# RF_LoRa___GPS.net
KiCad netlist of a schematic drawn in Altium Designer
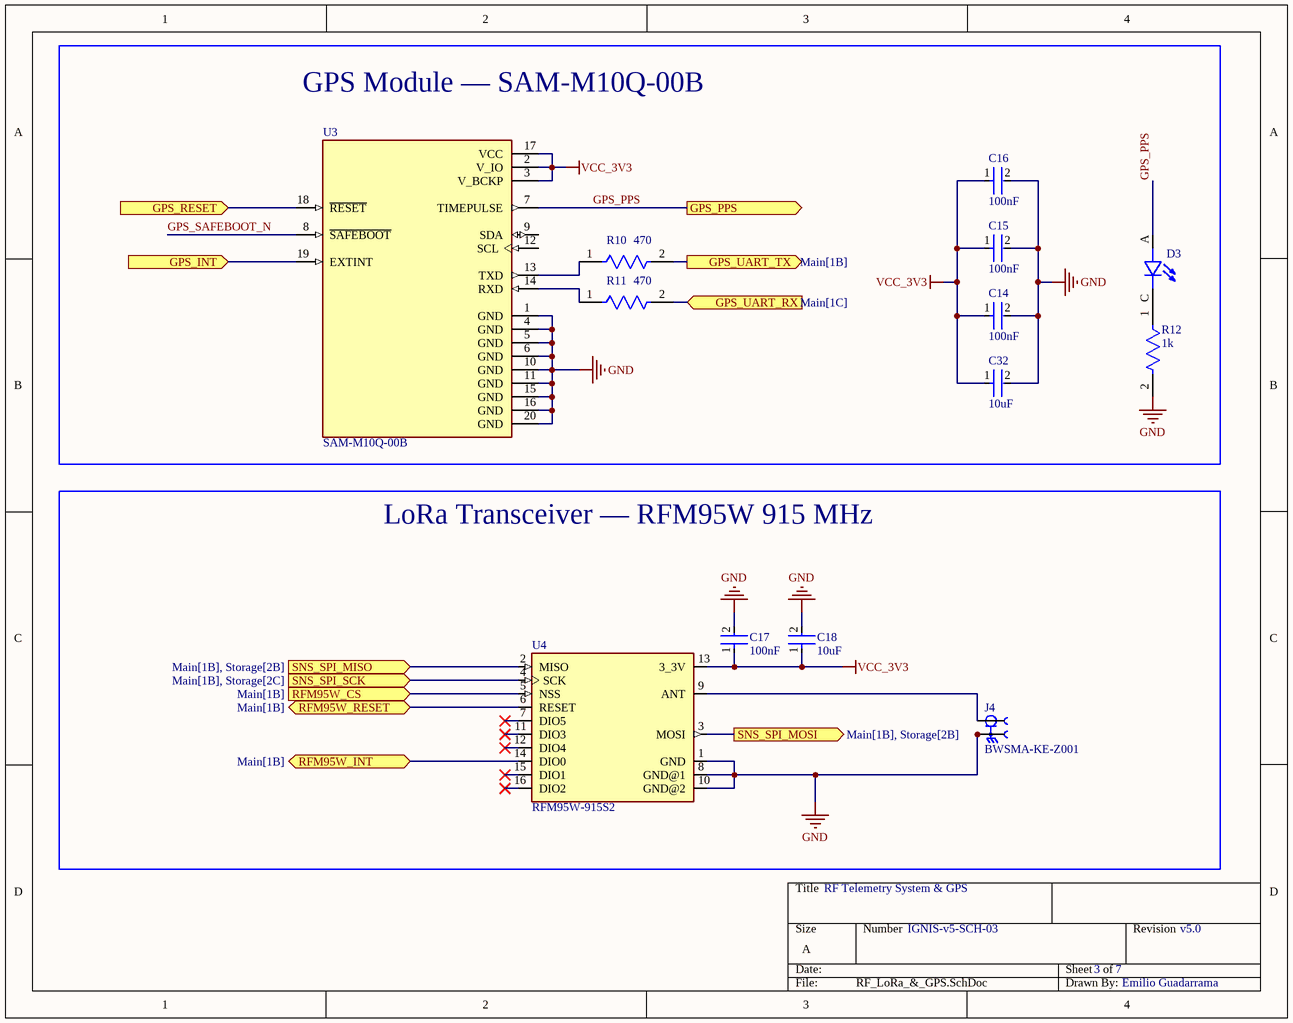
[diagram p0: RF_LoRa_&_GPS.SchDoc]

(export (version "E")
  (design (tool "Eeschema 10.0.6"))
  (components
    (comp (ref "C14")
      (value "100nF")
      (footprint "FP-C0805C-DN-MFG")
      (description "CAP CER 0.1UF 50V X7R 0805")
      (fields
        (field (name "MANUFACTURER PART NUMBER") "C0805C104K5RACTU")
        (field (name "MANUFACTURER") "KEMET")
      )
      (libsource (lib "Altium Content Vault") (part "b4654b650e69147ec39a6b967a45e02"))
    )
    (comp (ref "C15")
      (value "100nF")
      (footprint "FP-C0805C-DN-MFG")
      (description "CAP CER 0.1UF 50V X7R 0805")
      (fields
        (field (name "MANUFACTURER PART NUMBER") "C0805C104K5RACTU")
        (field (name "MANUFACTURER") "KEMET")
      )
      (libsource (lib "Altium Content Vault") (part "b4654b650e69147ec39a6b967a45e02"))
    )
    (comp (ref "C16")
      (value "100nF")
      (footprint "FP-C0805C-DN-MFG")
      (description "CAP CER 0.1UF 50V X7R 0805")
      (fields
        (field (name "MANUFACTURER PART NUMBER") "C0805C104K5RACTU")
        (field (name "MANUFACTURER") "KEMET")
      )
      (libsource (lib "Altium Content Vault") (part "b4654b650e69147ec39a6b967a45e02"))
    )
    (comp (ref "C17")
      (value "100nF")
      (footprint "FP-C0805C-DN-MFG")
      (description "CAP CER 0.1UF 50V X7R 0805")
      (fields
        (field (name "MANUFACTURER PART NUMBER") "C0805C104K5RACTU")
        (field (name "MANUFACTURER") "KEMET")
      )
      (libsource (lib "Altium Content Vault") (part "b4654b650e69147ec39a6b967a45e02"))
    )
    (comp (ref "C18")
      (value "10uF")
      (footprint "FP-C0805C-DN-MFG")
      (description "CAP CER 0.1UF 50V X7R 0805")
      (fields
        (field (name "MANUFACTURER PART NUMBER") "C0805C104K5RACTU")
        (field (name "MANUFACTURER") "KEMET")
      )
      (libsource (lib "Altium Content Vault") (part "b4654b650e69147ec39a6b967a45e02"))
    )
    (comp (ref "C32")
      (value "10uF")
      (footprint "FP-C0805C-DN-MFG")
      (description "CAP CER 0.1UF 50V X7R 0805")
      (fields
        (field (name "MANUFACTURER PART NUMBER") "C0805C104K5RACTU")
        (field (name "MANUFACTURER") "KEMET")
      )
      (libsource (lib "Altium Content Vault") (part "b4654b650e69147ec39a6b967a45e02"))
    )
    (comp (ref "D3")
      (value "SML-LXT0805IW-TR")
      (footprint "LEDC2012X120N")
      (fields (field (name "MF") "Lumex Opto/Components"))
      (libsource (lib "LED_0805-SML-LXT0805IW-TR") (part "SML-LXT0805IW-TR"))
    )
    (comp (ref "J4")
      (value "BWSMA-KE-Z001")
      (footprint "BAT_WIRELESS_BWSMA-KE-Z001")
      (fields (field (name "MF") "Bat Wireless"))
      (libsource (lib "SMA") (part "BWSMA-KE-Z001"))
    )
    (comp (ref "R10")
      (value "470")
      (footprint "FP-MCT0603-IPC_A")
      (description "RES SMD 100 OHM 1% 1/8W 0603")
      (fields (field (name "TOLERANCE") "0.1%"))
      (libsource (lib "Altium Content Vault") (part "1029c3af85768c4190bb7ad29bc67b5"))
    )
    (comp (ref "R11")
      (value "470")
      (footprint "FP-MCT0603-IPC_A")
      (description "RES SMD 100 OHM 1% 1/8W 0603")
      (fields (field (name "TOLERANCE") "0.1%"))
      (libsource (lib "Altium Content Vault") (part "1029c3af85768c4190bb7ad29bc67b5"))
    )
    (comp (ref "R12")
      (value "1k")
      (footprint "FP-MCT0603-IPC_A")
      (description "RES SMD 100 OHM 1% 1/8W 0603")
      (fields (field (name "TOLERANCE") "0.1%"))
      (libsource (lib "Altium Content Vault") (part "1029c3af85768c4190bb7ad29bc67b5"))
    )
    (comp (ref "U3")
      (value "SAM-M10Q-00B")
      (footprint "XCVR_SAM-M10Q-00B")
      (description "- RF Receiver Galileo, GLONASS, GPS 1.575GHz, 1.602GHz -165dBm 400kbps On-Board, Patch Module")
      (fields (field (name "MF") "u-blox"))
      (libsource (lib "SAM-M10Q-00B") (part "SAM-M10Q-00B"))
    )
    (comp (ref "U4")
      (value "RFM95W-915S2")
      (footprint "XCVR_RFM95W-868S2")
      (description "General ISM < 1GHz LoRa, Transceiver Module 915MHz Antenna Not Included Surface Mount")
      (fields (field (name "MF") "RF") (field (name "MP") "RFM95W-868S2"))
      (libsource (lib "RFM95W-915S2") (part "RFM95W-868S2"))
    )
  )
  (nets
    (net (code "1") (name "/GPS_INT") (class "Default")
      (node (ref "U3") (pin "19") (pinfunction "EXTINT_19") (pintype "input"))
    )
    (net (code "2") (name "/GPS_PPS") (class "Default")
      (node (ref "D3") (pin "A") (pinfunction "A_A") (pintype "passive"))
      (node (ref "U3") (pin "7") (pinfunction "TIMEPULSE_7") (pintype "output"))
    )
    (net (code "3") (name "/GPS_RESET") (class "Default")
      (node (ref "U3") (pin "18") (pinfunction "~{RESET}_18") (pintype "input"))
    )
    (net (code "4") (name "/GPS_SAFEBOOT_N") (class "Default")
      (node (ref "U3") (pin "8") (pinfunction "~{SAFEBOOT}_8") (pintype "input"))
    )
    (net (code "5") (name "/GPS_UART_RX") (class "Default")
      (node (ref "R11") (pin "2") (pinfunction "2_2") (pintype "passive"))
    )
    (net (code "6") (name "/GPS_UART_TX") (class "Default")
      (node (ref "R10") (pin "2") (pinfunction "2_2") (pintype "passive"))
    )
    (net (code "7") (name "/RFM95W_CS") (class "Default")
      (node (ref "U4") (pin "5") (pinfunction "NSS_5") (pintype "input"))
    )
    (net (code "8") (name "/RFM95W_INT") (class "Default")
      (node (ref "U4") (pin "14") (pinfunction "DIO0_14") (pintype "bidirectional"))
    )
    (net (code "9") (name "/RFM95W_RESET") (class "Default")
      (node (ref "U4") (pin "6") (pinfunction "RESET_6") (pintype "bidirectional"))
    )
    (net (code "10") (name "/SNS_SPI_MISO") (class "Default")
      (node (ref "U4") (pin "2") (pinfunction "MISO_2") (pintype "input"))
    )
    (net (code "11") (name "/SNS_SPI_MOSI") (class "Default")
      (node (ref "U4") (pin "3") (pinfunction "MOSI_3") (pintype "output"))
    )
    (net (code "12") (name "/SNS_SPI_SCK") (class "Default")
      (node (ref "U4") (pin "4") (pinfunction "SCK_4") (pintype "input"))
    )
    (net (code "13") (name "GND") (class "Default")
      (node (ref "C14") (pin "2") (pinfunction "2_2") (pintype "passive"))
      (node (ref "C15") (pin "2") (pinfunction "2_2") (pintype "passive"))
      (node (ref "C16") (pin "2") (pinfunction "2_2") (pintype "passive"))
      (node (ref "C17") (pin "2") (pinfunction "2_2") (pintype "passive"))
      (node (ref "C18") (pin "2") (pinfunction "2_2") (pintype "passive"))
      (node (ref "C32") (pin "2") (pinfunction "2_2") (pintype "passive"))
      (node (ref "J4") (pin "2_1") (pinfunction "2_2_1") (pintype "passive"))
      (node (ref "J4") (pin "2_2") (pinfunction "2_2_2") (pintype "passive"))
      (node (ref "J4") (pin "2_3") (pinfunction "2_2_3") (pintype "passive"))
      (node (ref "J4") (pin "2_4") (pinfunction "2_2_4") (pintype "passive"))
      (node (ref "R12") (pin "2") (pinfunction "2_2") (pintype "passive"))
      (node (ref "U3") (pin "1") (pinfunction "GND_1") (pintype "power_in"))
      (node (ref "U3") (pin "10") (pinfunction "GND_10") (pintype "power_in"))
      (node (ref "U3") (pin "11") (pinfunction "GND_11") (pintype "power_in"))
      (node (ref "U3") (pin "15") (pinfunction "GND_15") (pintype "power_in"))
      (node (ref "U3") (pin "16") (pinfunction "GND_16") (pintype "power_in"))
      (node (ref "U3") (pin "20") (pinfunction "GND_20") (pintype "power_in"))
      (node (ref "U3") (pin "4") (pinfunction "GND_4") (pintype "power_in"))
      (node (ref "U3") (pin "5") (pinfunction "GND_5") (pintype "power_in"))
      (node (ref "U3") (pin "6") (pinfunction "GND_6") (pintype "power_in"))
      (node (ref "U4") (pin "1") (pinfunction "GND_1") (pintype "power_in"))
      (node (ref "U4") (pin "10") (pinfunction "GND@2_10") (pintype "power_in"))
      (node (ref "U4") (pin "8") (pinfunction "GND@1_8") (pintype "power_in"))
    )
    (net (code "14") (name "Net-(D3-PadC)") (class "Default")
      (node (ref "D3") (pin "C") (pinfunction "C_C") (pintype "passive"))
      (node (ref "R12") (pin "1") (pinfunction "1_1") (pintype "passive"))
    )
    (net (code "15") (name "Net-(U3-RXD)") (class "Default")
      (node (ref "R11") (pin "1") (pinfunction "1_1") (pintype "passive"))
      (node (ref "U3") (pin "14") (pinfunction "RXD_14") (pintype "input"))
    )
    (net (code "16") (name "Net-(U3-TXD)") (class "Default")
      (node (ref "R10") (pin "1") (pinfunction "1_1") (pintype "passive"))
      (node (ref "U3") (pin "13") (pinfunction "TXD_13") (pintype "output"))
    )
    (net (code "17") (name "Net-(U4-ANT)") (class "Default")
      (node (ref "J4") (pin "1") (pinfunction "1_1") (pintype "passive"))
      (node (ref "U4") (pin "9") (pinfunction "ANT_9") (pintype "passive"))
    )
    (net (code "18") (name "VCC_3V3") (class "Default")
      (node (ref "C14") (pin "1") (pinfunction "1_1") (pintype "passive"))
      (node (ref "C15") (pin "1") (pinfunction "1_1") (pintype "passive"))
      (node (ref "C16") (pin "1") (pinfunction "1_1") (pintype "passive"))
      (node (ref "C17") (pin "1") (pinfunction "1_1") (pintype "passive"))
      (node (ref "C18") (pin "1") (pinfunction "1_1") (pintype "passive"))
      (node (ref "C32") (pin "1") (pinfunction "1_1") (pintype "passive"))
      (node (ref "U3") (pin "17") (pinfunction "VCC_17") (pintype "power_in"))
      (node (ref "U3") (pin "2") (pinfunction "V_IO_2") (pintype "power_in"))
      (node (ref "U3") (pin "3") (pinfunction "V_BCKP_3") (pintype "power_in"))
      (node (ref "U4") (pin "13") (pinfunction "3_3V_13") (pintype "power_in"))
    )
    (net (code "19") (name "unconnected-(U3-SCL-Pad12)") (class "Default")
      (node (ref "U3") (pin "12") (pinfunction "SCL_12") (pintype "input"))
    )
    (net (code "20") (name "unconnected-(U3-SDA-Pad9)") (class "Default")
      (node (ref "U3") (pin "9") (pinfunction "SDA_9") (pintype "bidirectional"))
    )
    (net (code "21") (name "unconnected-(U4-DIO1-Pad15)") (class "Default")
      (node (ref "U4") (pin "15") (pinfunction "DIO1_15") (pintype "bidirectional+no_connect"))
    )
    (net (code "22") (name "unconnected-(U4-DIO2-Pad16)") (class "Default")
      (node (ref "U4") (pin "16") (pinfunction "DIO2_16") (pintype "bidirectional+no_connect"))
    )
    (net (code "23") (name "unconnected-(U4-DIO3-Pad11)") (class "Default")
      (node (ref "U4") (pin "11") (pinfunction "DIO3_11") (pintype "bidirectional+no_connect"))
    )
    (net (code "24") (name "unconnected-(U4-DIO4-Pad12)") (class "Default")
      (node (ref "U4") (pin "12") (pinfunction "DIO4_12") (pintype "bidirectional+no_connect"))
    )
    (net (code "25") (name "unconnected-(U4-DIO5-Pad7)") (class "Default")
      (node (ref "U4") (pin "7") (pinfunction "DIO5_7") (pintype "bidirectional+no_connect"))
    )
  )
)
